# CAN.net
KiCad netlist of a schematic drawn in Altium Designer
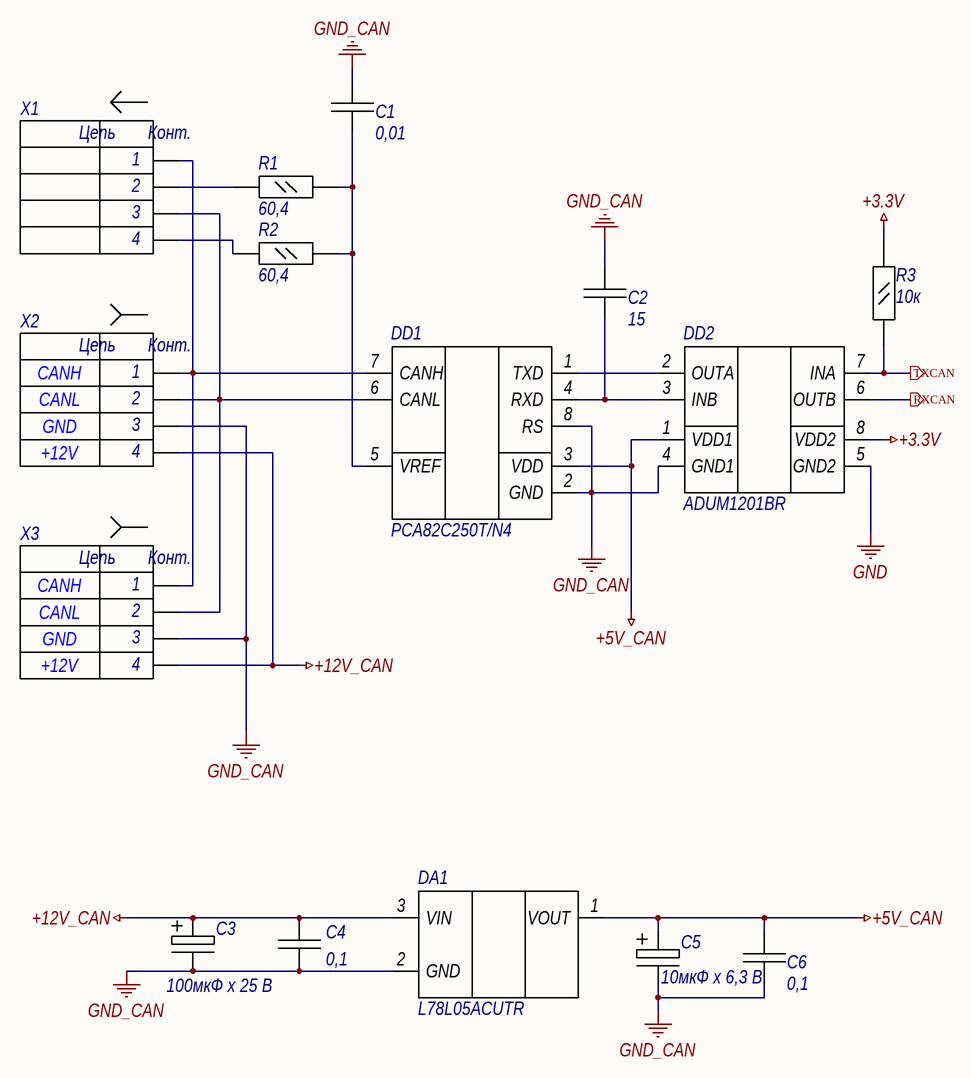
[diagram p0: CAN.SchDoc]

(export (version "E")
  (design (tool "Eeschema 10.0.6"))
  (components
    (comp (ref "C1")
      (value "0,01")
      (footprint "0805")
      (description "Конденсатор")
      (fields (field (name "MANUFACTURER") "YAGEO"))
      (libsource (lib "DX_test_lib2") (part "CC0805"))
    )
    (comp (ref "C2")
      (value "15")
      (footprint "0805")
      (description "Конденсатор")
      (fields (field (name "MANUFACTURER") "YAGEO"))
      (libsource (lib "DX_test_lib2") (part "CC0805"))
    )
    (comp (ref "C3")
      (value "100мкФ x 25 В")
      (footprint "C_D5/F2.0_V")
      (description "Выводные электролитические конденсаторы")
      (fields (field (name "MANUFACTURER") "HITANO"))
      (libsource (lib "DX_test_lib2") (part "CAP_RADIAL"))
    )
    (comp (ref "C4")
      (value "0,1")
      (footprint "0805")
      (description "Конденсатор")
      (fields (field (name "MANUFACTURER") "YAGEO"))
      (libsource (lib "DX_test_lib2") (part "CC0805"))
    )
    (comp (ref "C5")
      (value "10мкФ x 6,3 В")
      (footprint "CAP_TYPE_A")
      (fields (field (name "MANUFACTURER") "Vishay"))
      (libsource (lib "Capacitors") (part "TANTAL_A"))
    )
    (comp (ref "C6")
      (value "0,1")
      (footprint "0805")
      (description "Конденсатор")
      (fields (field (name "MANUFACTURER") "YAGEO"))
      (libsource (lib "DX_test_lib2") (part "CC0805"))
    )
    (comp (ref "DA1")
      (value "L78L05ACUTR")
      (footprint "SOT-89")
      (description "Линейный стабилизатор напряжения")
      (fields (field (name "MANUFACTURER") "STM"))
      (libsource (lib "DX_test_lib2") (part "L78L05ACU"))
    )
    (comp (ref "DD1")
      (value "PCA82C250T/N4")
      (footprint "SO-8")
      (description "Интерфейс физического уровня CAN")
      (fields (field (name "MANUFACTURER") "NXP"))
      (libsource (lib "Micro_Digital") (part "PCA82C250T"))
    )
    (comp (ref "DD2")
      (value "ADUM1201BR")
      (footprint "SO-8")
      (description "Изолятор цифрового сигнала")
      (fields (field (name "MANUFACTURER") "Analog Dev."))
      (libsource (lib "Micro_Digital") (part "ADUM1201"))
    )
    (comp (ref "R1")
      (value "60,4")
      (footprint "0805")
      (description "Резистор общего назначения 5%")
      (fields (field (name "MANUFACTURER") "YAGEO"))
      (libsource (lib "DX_test_lib2") (part "RC0805JR"))
    )
    (comp (ref "R2")
      (value "60,4")
      (footprint "0805")
      (description "Резистор общего назначения 5%")
      (fields (field (name "MANUFACTURER") "YAGEO"))
      (libsource (lib "DX_test_lib2") (part "RC0805JR"))
    )
    (comp (ref "R3")
      (value "10к")
      (footprint "0805")
      (description "Резистор общего назначения 5%")
      (fields (field (name "MANUFACTURER") "YAGEO"))
      (libsource (lib "DX_test_lib2") (part "RC0805JR"))
    )
    (comp (ref "X1")
      (value "PLD-4")
      (footprint "PLD-4")
      (description "Разъем, вилка на плату двухрядная, шаг 2.54мм")
      (libsource (lib "Connectors") (part "PLD-4"))
    )
    (comp (ref "X2")
      (value "TJ3-4P4C")
      (footprint "TJ3-4P4C")
      (description "Разъем, гнездо на плату, прямой")
      (libsource (lib "Connectors_TJ") (part "TJ3-4P4C"))
    )
    (comp (ref "X3")
      (value "TJ3-4P4C")
      (footprint "TJ3-4P4C")
      (description "Разъем, гнездо на плату, прямой")
      (libsource (lib "Connectors_TJ") (part "TJ3-4P4C"))
    )
  )
  (nets
    (net (code "1") (name "+3.3V") (class "Default")
      (node (ref "DD2") (pin "8") (pinfunction "VDD2_8") (pintype "passive"))
      (node (ref "R3") (pin "2") (pinfunction "2_2") (pintype "passive"))
    )
    (net (code "2") (name "+5V_CAN") (class "Default")
      (node (ref "C5") (pin "1") (pinfunction "1_1") (pintype "passive"))
      (node (ref "C6") (pin "1") (pinfunction "1_1") (pintype "passive"))
      (node (ref "DA1") (pin "1") (pinfunction "VOUT_1") (pintype "passive"))
      (node (ref "DD1") (pin "3") (pinfunction "VDD_3") (pintype "passive"))
      (node (ref "DD2") (pin "1") (pinfunction "VDD1_1") (pintype "passive"))
    )
    (net (code "3") (name "+12V_CAN") (class "Default")
      (node (ref "C3") (pin "1") (pinfunction "1_1") (pintype "passive"))
      (node (ref "C4") (pin "1") (pinfunction "1_1") (pintype "passive"))
      (node (ref "DA1") (pin "3") (pinfunction "VIN_3") (pintype "passive"))
      (node (ref "X2") (pin "4") (pinfunction "4_4") (pintype "passive"))
      (node (ref "X3") (pin "4") (pinfunction "4_4") (pintype "passive"))
    )
    (net (code "4") (name "/RXCAN") (class "Default")
      (node (ref "DD2") (pin "6") (pinfunction "OUTB_6") (pintype "passive"))
    )
    (net (code "5") (name "/TXCAN") (class "Default")
      (node (ref "DD2") (pin "7") (pinfunction "INA_7") (pintype "passive"))
      (node (ref "R3") (pin "1") (pinfunction "1_1") (pintype "passive"))
    )
    (net (code "6") (name "GND") (class "Default")
      (node (ref "DD2") (pin "5") (pinfunction "GND2_5") (pintype "passive"))
    )
    (net (code "7") (name "GND_CAN") (class "Default")
      (node (ref "C1") (pin "2") (pinfunction "2_2") (pintype "passive"))
      (node (ref "C2") (pin "2") (pinfunction "2_2") (pintype "passive"))
      (node (ref "C3") (pin "2") (pinfunction "2_2") (pintype "passive"))
      (node (ref "C4") (pin "2") (pinfunction "2_2") (pintype "passive"))
      (node (ref "C5") (pin "2") (pinfunction "2_2") (pintype "passive"))
      (node (ref "C6") (pin "2") (pinfunction "2_2") (pintype "passive"))
      (node (ref "DA1") (pin "2") (pinfunction "GND_2") (pintype "passive"))
      (node (ref "DD1") (pin "2") (pinfunction "GND_2") (pintype "passive"))
      (node (ref "DD1") (pin "8") (pinfunction "RS_8") (pintype "passive"))
      (node (ref "DD2") (pin "4") (pinfunction "GND1_4") (pintype "passive"))
      (node (ref "X2") (pin "3") (pinfunction "3_3") (pintype "passive"))
      (node (ref "X3") (pin "3") (pinfunction "3_3") (pintype "passive"))
    )
    (net (code "8") (name "Net-(DD1-CANH)") (class "Default")
      (node (ref "DD1") (pin "7") (pinfunction "CANH_7") (pintype "passive"))
      (node (ref "X1") (pin "1") (pinfunction "1_1") (pintype "passive"))
      (node (ref "X2") (pin "1") (pinfunction "1_1") (pintype "passive"))
      (node (ref "X3") (pin "1") (pinfunction "1_1") (pintype "passive"))
    )
    (net (code "9") (name "Net-(DD1-CANL)") (class "Default")
      (node (ref "DD1") (pin "6") (pinfunction "CANL_6") (pintype "passive"))
      (node (ref "X1") (pin "3") (pinfunction "3_3") (pintype "passive"))
      (node (ref "X2") (pin "2") (pinfunction "2_2") (pintype "passive"))
      (node (ref "X3") (pin "2") (pinfunction "2_2") (pintype "passive"))
    )
    (net (code "10") (name "Net-(DD1-RXD)") (class "Default")
      (node (ref "C2") (pin "1") (pinfunction "1_1") (pintype "passive"))
      (node (ref "DD1") (pin "4") (pinfunction "RXD_4") (pintype "passive"))
      (node (ref "DD2") (pin "3") (pinfunction "INB_3") (pintype "passive"))
    )
    (net (code "11") (name "Net-(DD1-TXD)") (class "Default")
      (node (ref "DD1") (pin "1") (pinfunction "TXD_1") (pintype "passive"))
      (node (ref "DD2") (pin "2") (pinfunction "OUTA_2") (pintype "passive"))
    )
    (net (code "12") (name "Net-(DD1-VREF)") (class "Default")
      (node (ref "C1") (pin "1") (pinfunction "1_1") (pintype "passive"))
      (node (ref "DD1") (pin "5") (pinfunction "VREF_5") (pintype "passive"))
      (node (ref "R1") (pin "2") (pinfunction "2_2") (pintype "passive"))
      (node (ref "R2") (pin "2") (pinfunction "2_2") (pintype "passive"))
    )
    (net (code "13") (name "Net-(R1-Pad1)") (class "Default")
      (node (ref "R1") (pin "1") (pinfunction "1_1") (pintype "passive"))
      (node (ref "X1") (pin "2") (pinfunction "2_2") (pintype "passive"))
    )
    (net (code "14") (name "Net-(R2-Pad1)") (class "Default")
      (node (ref "R2") (pin "1") (pinfunction "1_1") (pintype "passive"))
      (node (ref "X1") (pin "4") (pinfunction "4_4") (pintype "passive"))
    )
  )
)
